# sensores.net
KiCad netlist of a schematic drawn in Altium Designer
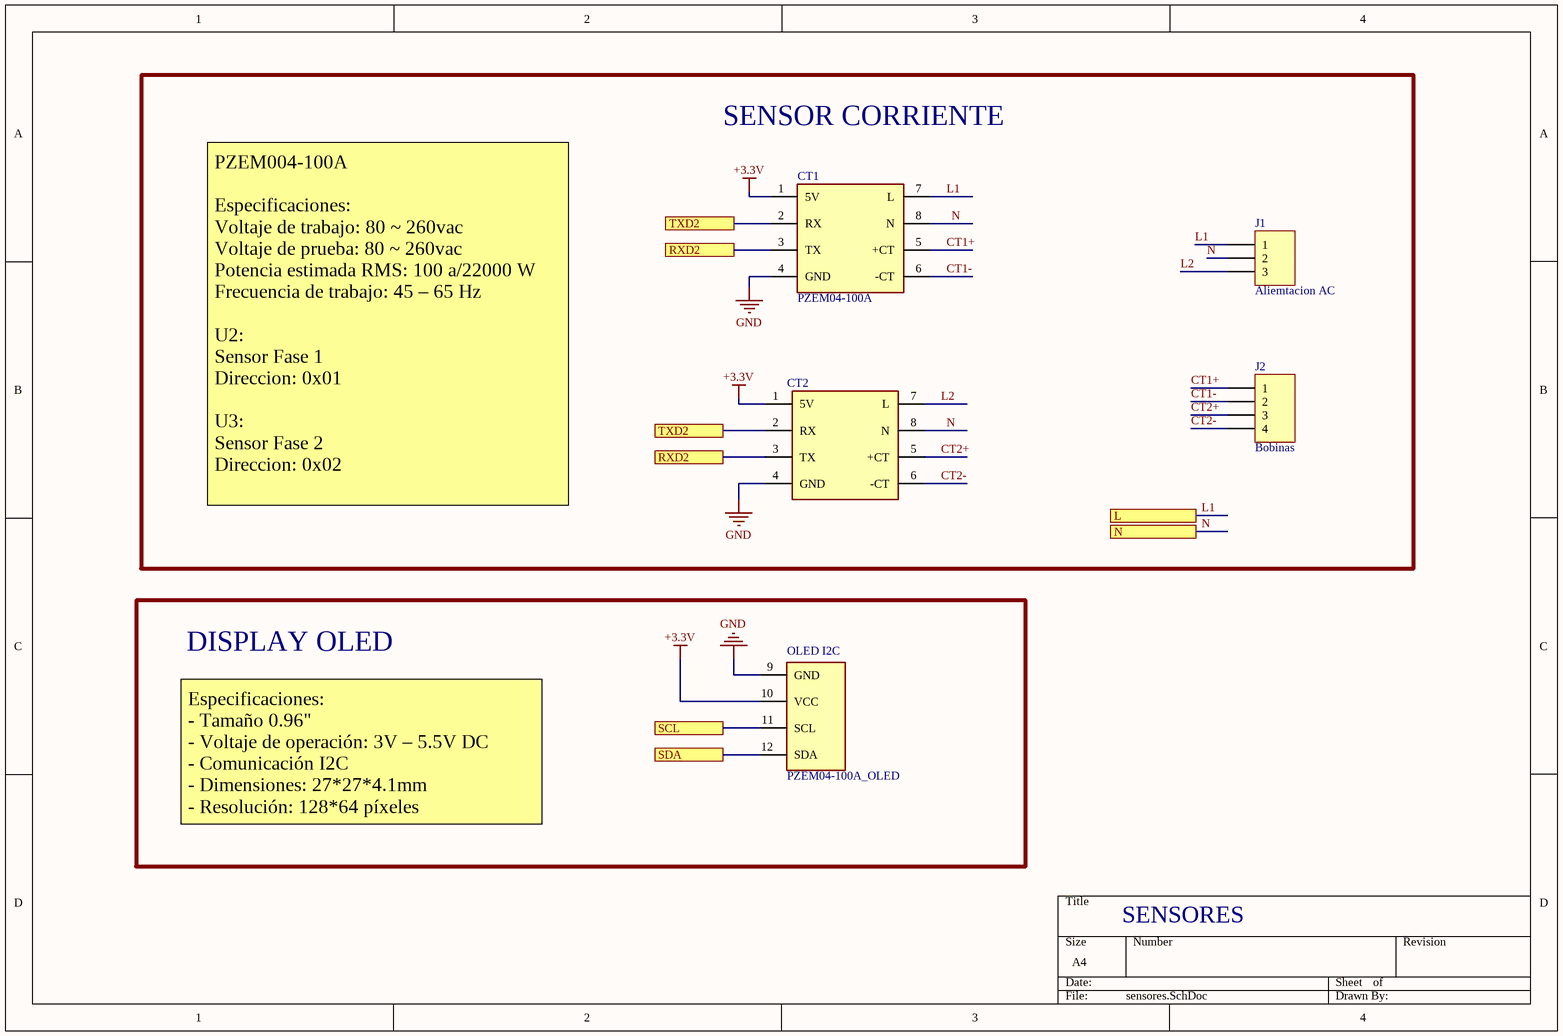
[diagram p0: sensores.SchDoc]

(export (version "E")
  (design (tool "Eeschema 10.0.6"))
  (components
    (comp (ref "CT1")
      (value "PZEM04-100A")
      (footprint "FP-PZEM-004-100A")
      (description "Sensor Pzem004 Version 100A")
      (libsource (lib "Simbologia") (part "PZEM04-100A"))
    )
    (comp (ref "CT2")
      (value "PZEM04-100A_OLED")
      (footprint "PZEM100A-OLED")
      (description "Sensor Pzem004 Version 100A\r\n\r\nOLED I2C 0.96")
      (libsource (lib "Simbologia") (part "PZEM04-100A_OLED"))
    )
    (comp (ref "J1")
      (value "Aliemtacion AC")
      (footprint "Bornera 3")
      (libsource (lib "user_conector") (part "Conector 3"))
    )
    (comp (ref "J2")
      (value "Bobinas")
      (footprint "BORNERA 4")
      (libsource (lib "user_conector") (part "Conector 4"))
    )
  )
  (nets
    (net (code "1") (name "+3.3V") (class "Default")
      (node (ref "CT1") (pin "1") (pinfunction "5V_1") (pintype "power_in"))
      (node (ref "CT2") (pin "1") (pinfunction "5V_1") (pintype "power_in"))
      (node (ref "CT2") (pin "10") (pinfunction "VCC_10") (pintype "power_in"))
    )
    (net (code "2") (name "/CT1+") (class "Default")
      (node (ref "CT1") (pin "5") (pinfunction "+CT_5") (pintype "power_in"))
      (node (ref "J2") (pin "1") (pinfunction "1_1") (pintype "passive"))
    )
    (net (code "3") (name "/CT1-") (class "Default")
      (node (ref "CT1") (pin "6") (pinfunction "-CT_6") (pintype "power_in"))
      (node (ref "J2") (pin "2") (pinfunction "2_2") (pintype "passive"))
    )
    (net (code "4") (name "/CT2+") (class "Default")
      (node (ref "CT2") (pin "5") (pinfunction "+CT_5") (pintype "power_in"))
      (node (ref "J2") (pin "3") (pinfunction "3_3") (pintype "passive"))
    )
    (net (code "5") (name "/CT2-") (class "Default")
      (node (ref "CT2") (pin "6") (pinfunction "-CT_6") (pintype "power_in"))
      (node (ref "J2") (pin "4") (pinfunction "4_4") (pintype "passive"))
    )
    (net (code "6") (name "/L1") (class "Default")
      (node (ref "CT1") (pin "7") (pinfunction "L_7") (pintype "power_in"))
      (node (ref "J1") (pin "1") (pinfunction "1_1") (pintype "passive"))
    )
    (net (code "7") (name "/L2") (class "Default")
      (node (ref "CT2") (pin "7") (pinfunction "L_7") (pintype "power_in"))
      (node (ref "J1") (pin "3") (pinfunction "3_3") (pintype "passive"))
    )
    (net (code "8") (name "/N") (class "Default")
      (node (ref "CT1") (pin "8") (pinfunction "N_8") (pintype "power_in"))
      (node (ref "CT2") (pin "8") (pinfunction "N_8") (pintype "power_in"))
      (node (ref "J1") (pin "2") (pinfunction "2_2") (pintype "passive"))
    )
    (net (code "9") (name "/RXD2") (class "Default")
      (node (ref "CT1") (pin "3") (pinfunction "TX_3") (pintype "power_in"))
      (node (ref "CT2") (pin "3") (pinfunction "TX_3") (pintype "power_in"))
    )
    (net (code "10") (name "/SCL") (class "Default")
      (node (ref "CT2") (pin "11") (pinfunction "SCL_11") (pintype "power_in"))
    )
    (net (code "11") (name "/SDA") (class "Default")
      (node (ref "CT2") (pin "12") (pinfunction "SDA_12") (pintype "power_in"))
    )
    (net (code "12") (name "/TXD2") (class "Default")
      (node (ref "CT1") (pin "2") (pinfunction "RX_2") (pintype "power_in"))
      (node (ref "CT2") (pin "2") (pinfunction "RX_2") (pintype "power_in"))
    )
    (net (code "13") (name "GND") (class "Default")
      (node (ref "CT1") (pin "4") (pinfunction "GND_4") (pintype "power_in"))
      (node (ref "CT2") (pin "4") (pinfunction "GND_4") (pintype "power_in"))
      (node (ref "CT2") (pin "9") (pinfunction "GND_9") (pintype "power_in"))
    )
  )
)
